# DClink.net
KiCad netlist of a schematic drawn in Altium Designer
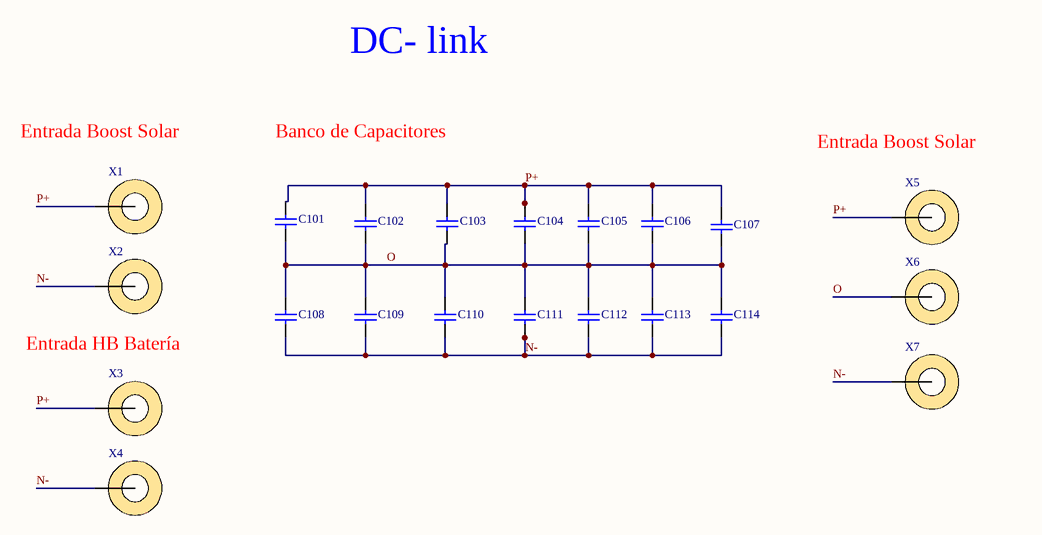
[diagram p0: DClink.SchDoc]

(export (version "E")
  (design (tool "Eeschema 10.0.6"))
  (components
    (comp (ref "C101")
      (value "100nF")
      (footprint "CAP_EL450_ALC70C152EN450")
      (description "0.1µF ±10% 50V Ceramic Capacitor X7R 1206 (3216 Metric)")
      (fields (field (name "MF") "KEMET") (field (name "CREATED") "2020_06_15_DAarancibia"))
      (libsource (lib "Schlib1") (part "Cap_HV_El_ ALC70C152EN450"))
    )
    (comp (ref "C102")
      (value "100nF")
      (footprint "CAP_EL450_ALC70C152EN450")
      (description "0.1µF ±10% 50V Ceramic Capacitor X7R 1206 (3216 Metric)")
      (fields (field (name "MF") "KEMET") (field (name "CREATED") "2020_06_15_DAarancibia"))
      (libsource (lib "Schlib1") (part "Cap_HV_El_ ALC70C152EN450"))
    )
    (comp (ref "C103")
      (value "100nF")
      (footprint "CAP_EL450_ALC70C152EN450")
      (description "0.1µF ±10% 50V Ceramic Capacitor X7R 1206 (3216 Metric)")
      (fields (field (name "MF") "KEMET") (field (name "CREATED") "2020_06_15_DAarancibia"))
      (libsource (lib "Schlib1") (part "Cap_HV_El_ ALC70C152EN450"))
    )
    (comp (ref "C104")
      (value "100nF")
      (footprint "CAP_EL450_ALC70C152EN450")
      (description "0.1µF ±10% 50V Ceramic Capacitor X7R 1206 (3216 Metric)")
      (fields (field (name "MF") "KEMET") (field (name "CREATED") "2020_06_15_DAarancibia"))
      (libsource (lib "Schlib1") (part "Cap_HV_El_ ALC70C152EN450"))
    )
    (comp (ref "C105")
      (value "100nF")
      (footprint "CAP_EL450_ALC70C152EN450")
      (description "0.1µF ±10% 50V Ceramic Capacitor X7R 1206 (3216 Metric)")
      (fields (field (name "MF") "KEMET") (field (name "CREATED") "2020_06_15_DAarancibia"))
      (libsource (lib "Schlib1") (part "Cap_HV_El_ ALC70C152EN450"))
    )
    (comp (ref "C106")
      (value "100nF")
      (footprint "CAP_EL450_ALC70C152EN450")
      (description "0.1µF ±10% 50V Ceramic Capacitor X7R 1206 (3216 Metric)")
      (fields (field (name "MF") "KEMET") (field (name "CREATED") "2020_06_15_DAarancibia"))
      (libsource (lib "Schlib1") (part "Cap_HV_El_ ALC70C152EN450"))
    )
    (comp (ref "C107")
      (value "100nF")
      (footprint "CAP_EL450_ALC70C152EN450")
      (description "0.1µF ±10% 50V Ceramic Capacitor X7R 1206 (3216 Metric)")
      (fields (field (name "MF") "KEMET") (field (name "CREATED") "2020_06_15_DAarancibia"))
      (libsource (lib "Schlib1") (part "Cap_HV_El_ ALC70C152EN450"))
    )
    (comp (ref "C108")
      (value "100nF")
      (footprint "CAP_EL450_ALC70C152EN450")
      (description "0.1µF ±10% 50V Ceramic Capacitor X7R 1206 (3216 Metric)")
      (fields (field (name "MF") "KEMET") (field (name "CREATED") "2020_06_15_DAarancibia"))
      (libsource (lib "Schlib1") (part "Cap_HV_El_ ALC70C152EN450"))
    )
    (comp (ref "C109")
      (value "100nF")
      (footprint "CAP_EL450_ALC70C152EN450")
      (description "0.1µF ±10% 50V Ceramic Capacitor X7R 1206 (3216 Metric)")
      (fields (field (name "MF") "KEMET") (field (name "CREATED") "2020_06_15_DAarancibia"))
      (libsource (lib "Schlib1") (part "Cap_HV_El_ ALC70C152EN450"))
    )
    (comp (ref "C110")
      (value "100nF")
      (footprint "CAP_EL450_ALC70C152EN450")
      (description "0.1µF ±10% 50V Ceramic Capacitor X7R 1206 (3216 Metric)")
      (fields (field (name "MF") "KEMET") (field (name "CREATED") "2020_06_15_DAarancibia"))
      (libsource (lib "Schlib1") (part "Cap_HV_El_ ALC70C152EN450"))
    )
    (comp (ref "C111")
      (value "100nF")
      (footprint "CAP_EL450_ALC70C152EN450")
      (description "0.1µF ±10% 50V Ceramic Capacitor X7R 1206 (3216 Metric)")
      (fields (field (name "MF") "KEMET") (field (name "CREATED") "2020_06_15_DAarancibia"))
      (libsource (lib "Schlib1") (part "Cap_HV_El_ ALC70C152EN450"))
    )
    (comp (ref "C112")
      (value "100nF")
      (footprint "CAP_EL450_ALC70C152EN450")
      (description "0.1µF ±10% 50V Ceramic Capacitor X7R 1206 (3216 Metric)")
      (fields (field (name "MF") "KEMET") (field (name "CREATED") "2020_06_15_DAarancibia"))
      (libsource (lib "Schlib1") (part "Cap_HV_El_ ALC70C152EN450"))
    )
    (comp (ref "C113")
      (value "100nF")
      (footprint "CAP_EL450_ALC70C152EN450")
      (description "0.1µF ±10% 50V Ceramic Capacitor X7R 1206 (3216 Metric)")
      (fields (field (name "MF") "KEMET") (field (name "CREATED") "2020_06_15_DAarancibia"))
      (libsource (lib "Schlib1") (part "Cap_HV_El_ ALC70C152EN450"))
    )
    (comp (ref "C114")
      (value "100nF")
      (footprint "CAP_EL450_ALC70C152EN450")
      (description "0.1µF ±10% 50V Ceramic Capacitor X7R 1206 (3216 Metric)")
      (fields (field (name "MF") "KEMET") (field (name "CREATED") "2020_06_15_DAarancibia"))
      (libsource (lib "Schlib1") (part "Cap_HV_El_ ALC70C152EN450"))
    )
    (comp (ref "X1")
      (value "M6 Pad")
      (footprint "M6 PAD Connector")
      (description "Pad M6")
      (fields (field (name "CREATED") "2021_07_09_DArancibia"))
      (libsource (lib "H-Bridge 3-Leg - Lib") (part "Con_Pad_M6"))
    )
    (comp (ref "X2")
      (value "M6 Pad")
      (footprint "M6 PAD Connector")
      (description "Pad M6")
      (fields (field (name "CREATED") "2021_07_09_DArancibia"))
      (libsource (lib "H-Bridge 3-Leg - Lib") (part "Con_Pad_M6"))
    )
    (comp (ref "X3")
      (value "M6 Pad")
      (footprint "M6 PAD Connector")
      (description "Pad M6")
      (fields (field (name "CREATED") "2021_07_09_DArancibia"))
      (libsource (lib "H-Bridge 3-Leg - Lib") (part "Con_Pad_M6"))
    )
    (comp (ref "X4")
      (value "M6 Pad")
      (footprint "M6 PAD Connector")
      (description "Pad M6")
      (fields (field (name "CREATED") "2021_07_09_DArancibia"))
      (libsource (lib "H-Bridge 3-Leg - Lib") (part "Con_Pad_M6"))
    )
    (comp (ref "X5")
      (value "M6 Pad")
      (footprint "M6 PAD Connector")
      (description "Pad M6")
      (fields (field (name "CREATED") "2021_07_09_DArancibia"))
      (libsource (lib "H-Bridge 3-Leg - Lib") (part "Con_Pad_M6"))
    )
    (comp (ref "X6")
      (value "M6 Pad")
      (footprint "M6 PAD Connector")
      (description "Pad M6")
      (fields (field (name "CREATED") "2021_07_09_DArancibia"))
      (libsource (lib "H-Bridge 3-Leg - Lib") (part "Con_Pad_M6"))
    )
    (comp (ref "X7")
      (value "M6 Pad")
      (footprint "M6 PAD Connector")
      (description "Pad M6")
      (fields (field (name "CREATED") "2021_07_09_DArancibia"))
      (libsource (lib "H-Bridge 3-Leg - Lib") (part "Con_Pad_M6"))
    )
  )
  (nets
    (net (code "1") (name "/N-") (class "Default")
      (node (ref "C108") (pin "2") (pinfunction "2_2") (pintype "passive"))
      (node (ref "C109") (pin "2") (pinfunction "2_2") (pintype "passive"))
      (node (ref "C110") (pin "2") (pinfunction "2_2") (pintype "passive"))
      (node (ref "C111") (pin "2") (pinfunction "2_2") (pintype "passive"))
      (node (ref "C112") (pin "2") (pinfunction "2_2") (pintype "passive"))
      (node (ref "C113") (pin "2") (pinfunction "2_2") (pintype "passive"))
      (node (ref "C114") (pin "2") (pinfunction "2_2") (pintype "passive"))
      (node (ref "X2") (pin "1") (pinfunction "1_1") (pintype "passive"))
      (node (ref "X4") (pin "1") (pinfunction "1_1") (pintype "passive"))
      (node (ref "X7") (pin "1") (pinfunction "1_1") (pintype "passive"))
    )
    (net (code "2") (name "/O") (class "Default")
      (node (ref "C101") (pin "2") (pinfunction "2_2") (pintype "passive"))
      (node (ref "C102") (pin "2") (pinfunction "2_2") (pintype "passive"))
      (node (ref "C103") (pin "2") (pinfunction "2_2") (pintype "passive"))
      (node (ref "C104") (pin "2") (pinfunction "2_2") (pintype "passive"))
      (node (ref "C105") (pin "2") (pinfunction "2_2") (pintype "passive"))
      (node (ref "C106") (pin "2") (pinfunction "2_2") (pintype "passive"))
      (node (ref "C107") (pin "2") (pinfunction "2_2") (pintype "passive"))
      (node (ref "C108") (pin "1") (pinfunction "1_1") (pintype "passive"))
      (node (ref "C109") (pin "1") (pinfunction "1_1") (pintype "passive"))
      (node (ref "C110") (pin "1") (pinfunction "1_1") (pintype "passive"))
      (node (ref "C111") (pin "1") (pinfunction "1_1") (pintype "passive"))
      (node (ref "C112") (pin "1") (pinfunction "1_1") (pintype "passive"))
      (node (ref "C113") (pin "1") (pinfunction "1_1") (pintype "passive"))
      (node (ref "C114") (pin "1") (pinfunction "1_1") (pintype "passive"))
      (node (ref "X6") (pin "1") (pinfunction "1_1") (pintype "passive"))
    )
    (net (code "3") (name "/P+") (class "Default")
      (node (ref "C101") (pin "1") (pinfunction "1_1") (pintype "passive"))
      (node (ref "C102") (pin "1") (pinfunction "1_1") (pintype "passive"))
      (node (ref "C103") (pin "1") (pinfunction "1_1") (pintype "passive"))
      (node (ref "C104") (pin "1") (pinfunction "1_1") (pintype "passive"))
      (node (ref "C105") (pin "1") (pinfunction "1_1") (pintype "passive"))
      (node (ref "C106") (pin "1") (pinfunction "1_1") (pintype "passive"))
      (node (ref "C107") (pin "1") (pinfunction "1_1") (pintype "passive"))
      (node (ref "X1") (pin "1") (pinfunction "1_1") (pintype "passive"))
      (node (ref "X3") (pin "1") (pinfunction "1_1") (pintype "passive"))
      (node (ref "X5") (pin "1") (pinfunction "1_1") (pintype "passive"))
    )
  )
)
